# arduino.net
KiCad netlist of a schematic drawn in EAGLE
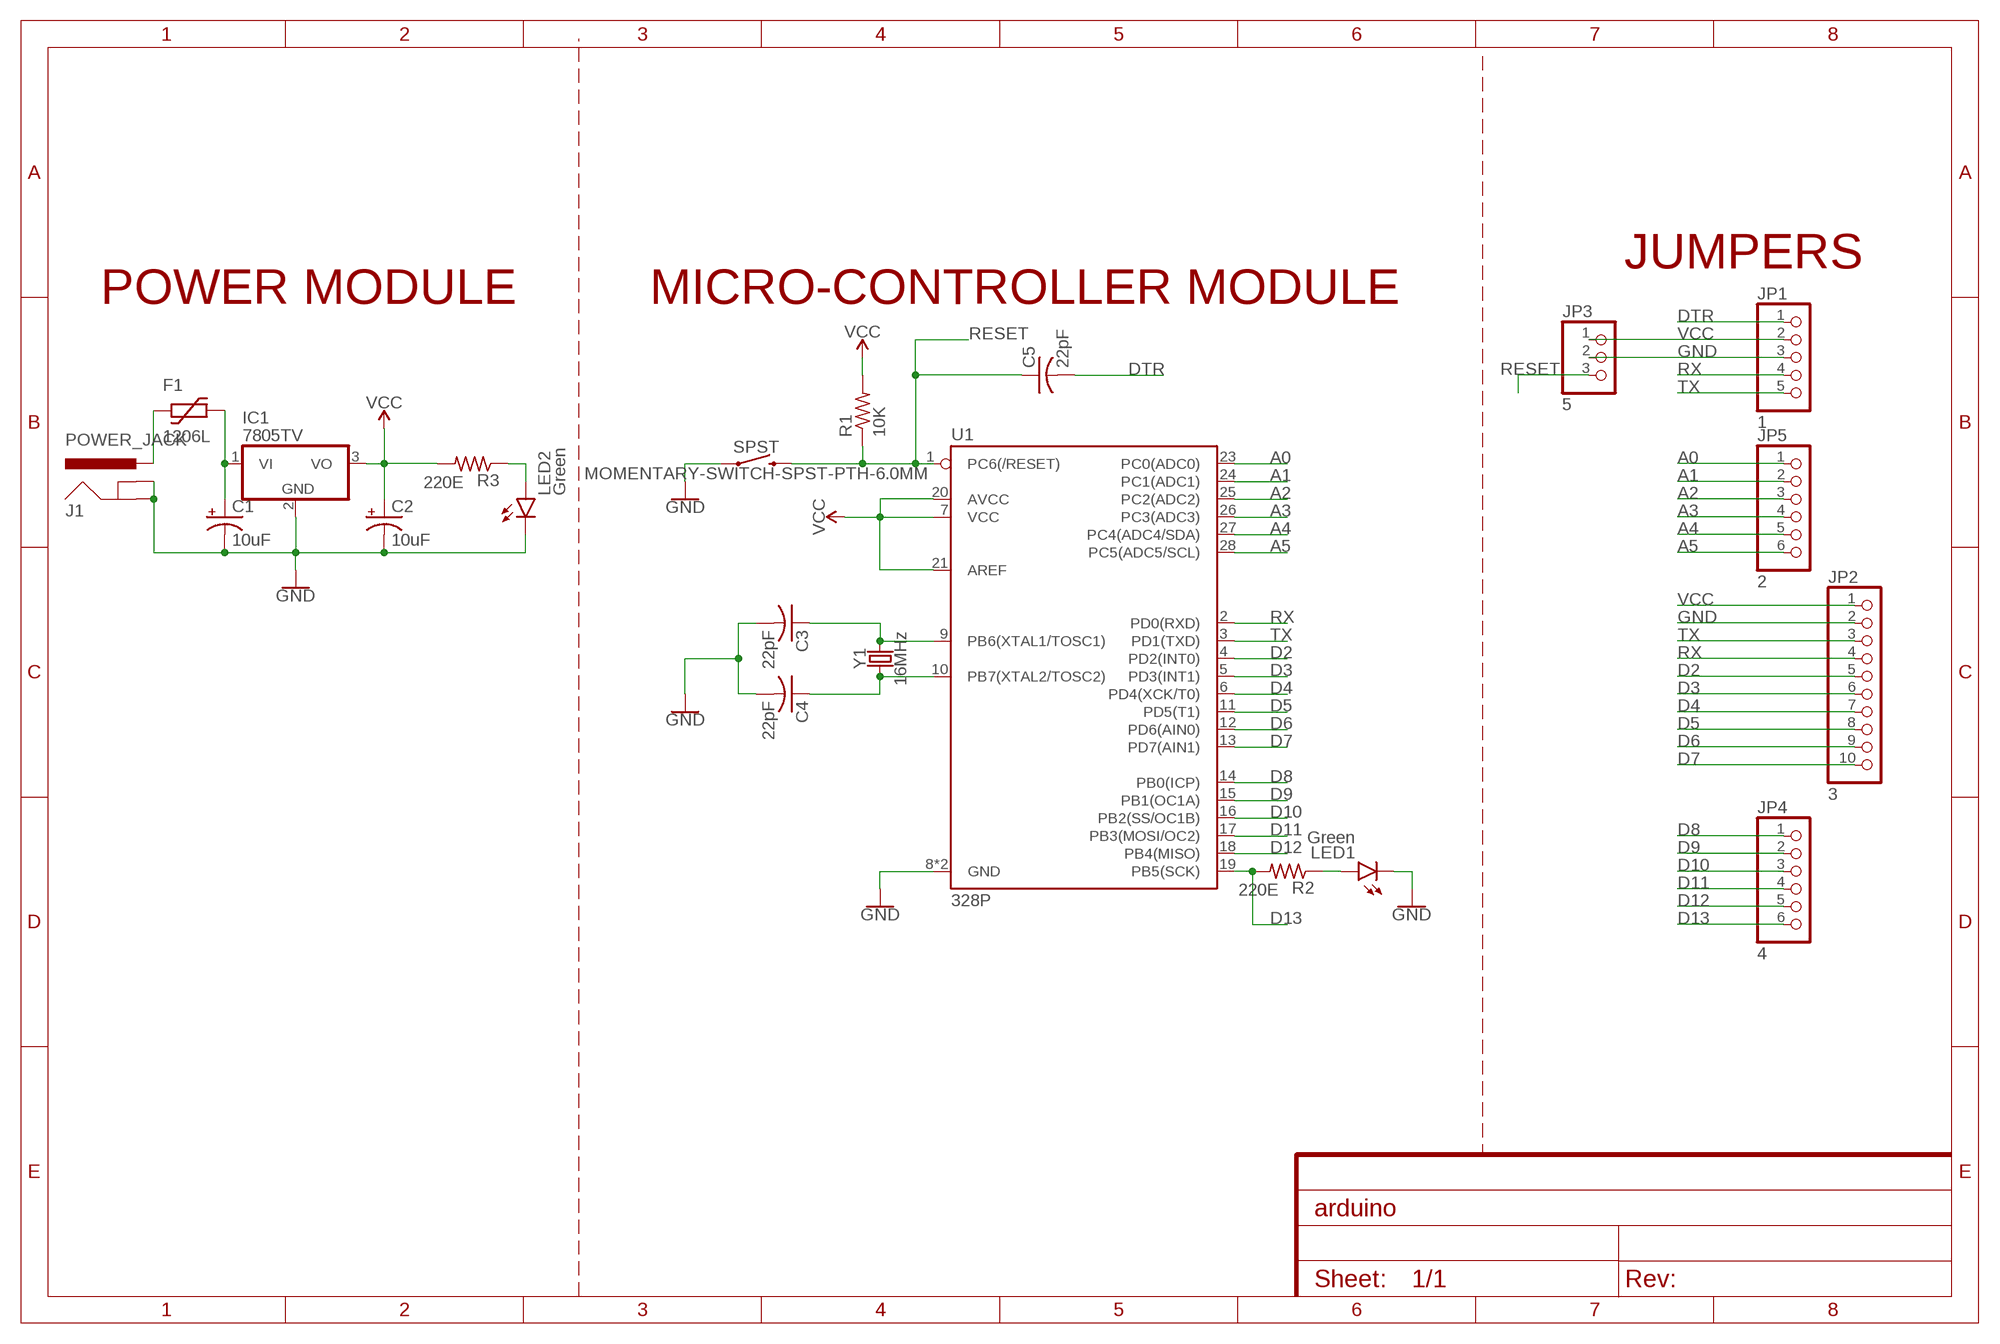
[diagram p0: schematic, sheet 1]

(export (version "E")
  (design (tool "Eeschema 10.0.6"))
  (components
    (comp (ref "C1")
      (value "10uF")
      (footprint "eagle-import:E2,5-6E")
      (libsource (lib "eagle-import") (part "CPOL-USE2,5-6E"))
    )
    (comp (ref "C2")
      (value "10uF")
      (footprint "eagle-import:E2,5-6E")
      (libsource (lib "eagle-import") (part "CPOL-USE2,5-6E"))
    )
    (comp (ref "C3")
      (value "22pF")
      (footprint "eagle-import:C025-024X044")
      (libsource (lib "eagle-import") (part "C-US025-024X044"))
    )
    (comp (ref "C4")
      (value "22pF")
      (footprint "eagle-import:C025-024X044")
      (libsource (lib "eagle-import") (part "C-US025-024X044"))
    )
    (comp (ref "C5")
      (value "22pF")
      (footprint "eagle-import:C025-024X044")
      (libsource (lib "eagle-import") (part "C-US025-024X044"))
    )
    (comp (ref "F1")
      (value "1206L")
      (footprint "eagle-import:1206L")
      (libsource (lib "eagle-import") (part "1206L"))
    )
    (comp (ref "IC1")
      (value "7805TV")
      (footprint "eagle-import:TO220V")
      (libsource (lib "eagle-import") (part "78TV05"))
    )
    (comp (ref "J1")
      (value "POWER_JACK")
      (footprint "eagle-import:POWER_JACK_PTH")
      (libsource (lib "eagle-import") (part "POWER_JACK"))
    )
    (comp (ref "JP1")
      (value "1")
      (footprint "eagle-import:1X05")
      (libsource (lib "eagle-import") (part "PINHD-1X5"))
    )
    (comp (ref "JP2")
      (value "3")
      (footprint "eagle-import:1X10")
      (libsource (lib "eagle-import") (part "PINHD-1X10"))
    )
    (comp (ref "JP3")
      (value "5")
      (footprint "eagle-import:1X03")
      (libsource (lib "eagle-import") (part "PINHD-1X3"))
    )
    (comp (ref "JP4")
      (value "4")
      (footprint "eagle-import:1X06")
      (libsource (lib "eagle-import") (part "PINHD-1X6"))
    )
    (comp (ref "JP5")
      (value "2")
      (footprint "eagle-import:1X06")
      (libsource (lib "eagle-import") (part "PINHD-1X6"))
    )
    (comp (ref "LED1")
      (value "Green")
      (footprint "eagle-import:LED3MM")
      (libsource (lib "eagle-import") (part "LED3MM"))
    )
    (comp (ref "LED2")
      (value "Green")
      (footprint "eagle-import:LED3MM")
      (libsource (lib "eagle-import") (part "LED3MM"))
    )
    (comp (ref "R1")
      (value "10K")
      (footprint "eagle-import:0204_7")
      (libsource (lib "eagle-import") (part "R-US_0204/7"))
    )
    (comp (ref "R2")
      (value "220E")
      (footprint "eagle-import:0204_7")
      (libsource (lib "eagle-import") (part "R-US_0204/7"))
    )
    (comp (ref "R3")
      (value "220E")
      (footprint "eagle-import:0204_7")
      (libsource (lib "eagle-import") (part "R-US_0204/7"))
    )
    (comp (ref "SPST")
      (value "MOMENTARY-SWITCH-SPST-PTH-6.0MM")
      (footprint "eagle-import:TACTILE_SWITCH_PTH_6.0MM")
      (libsource (lib "eagle-import") (part "MOMENTARY-SWITCH-SPST-PTH-6.0MM"))
    )
    (comp (ref "U1")
      (value "328P")
      (footprint "eagle-import:DIP28")
      (libsource (lib "eagle-import") (part "ATMEGA328P_PDIP"))
    )
    (comp (ref "Y1")
      (value "16MHz")
      (footprint "eagle-import:HC49US")
      (libsource (lib "eagle-import") (part "CRYSTAL-16MHZPTH-HC49US"))
    )
  )
  (nets
    (net (code "1") (name "/A0") (class "Default")
      (node (ref "JP5") (pin "1") (pinfunction "1_1") (pintype "passive"))
      (node (ref "U1") (pin "23") (pinfunction "PC0(ADC0)_23") (pintype "bidirectional"))
    )
    (net (code "2") (name "/A1") (class "Default")
      (node (ref "JP5") (pin "2") (pinfunction "2_2") (pintype "passive"))
      (node (ref "U1") (pin "24") (pinfunction "PC1(ADC1)_24") (pintype "bidirectional"))
    )
    (net (code "3") (name "/A2") (class "Default")
      (node (ref "JP5") (pin "3") (pinfunction "3_3") (pintype "passive"))
      (node (ref "U1") (pin "25") (pinfunction "PC2(ADC2)_25") (pintype "bidirectional"))
    )
    (net (code "4") (name "/A3") (class "Default")
      (node (ref "JP5") (pin "4") (pinfunction "4_4") (pintype "passive"))
      (node (ref "U1") (pin "26") (pinfunction "PC3(ADC3)_26") (pintype "bidirectional"))
    )
    (net (code "5") (name "/A4") (class "Default")
      (node (ref "JP5") (pin "5") (pinfunction "5_5") (pintype "passive"))
      (node (ref "U1") (pin "27") (pinfunction "PC4(ADC4/SDA)_27") (pintype "bidirectional"))
    )
    (net (code "6") (name "/A5") (class "Default")
      (node (ref "JP5") (pin "6") (pinfunction "6_6") (pintype "passive"))
      (node (ref "U1") (pin "28") (pinfunction "PC5(ADC5/SCL)_28") (pintype "bidirectional"))
    )
    (net (code "7") (name "/D2") (class "Default")
      (node (ref "JP2") (pin "5") (pinfunction "5_5") (pintype "passive"))
      (node (ref "U1") (pin "4") (pinfunction "PD2(INT0)_4") (pintype "bidirectional"))
    )
    (net (code "8") (name "/D3") (class "Default")
      (node (ref "JP2") (pin "6") (pinfunction "6_6") (pintype "passive"))
      (node (ref "U1") (pin "5") (pinfunction "PD3(INT1)_5") (pintype "bidirectional"))
    )
    (net (code "9") (name "/D4") (class "Default")
      (node (ref "JP2") (pin "7") (pinfunction "7_7") (pintype "passive"))
      (node (ref "U1") (pin "6") (pinfunction "PD4(XCK/T0)_6") (pintype "bidirectional"))
    )
    (net (code "10") (name "/D5") (class "Default")
      (node (ref "JP2") (pin "8") (pinfunction "8_8") (pintype "passive"))
      (node (ref "U1") (pin "11") (pinfunction "PD5(T1)_11") (pintype "bidirectional"))
    )
    (net (code "11") (name "/D6") (class "Default")
      (node (ref "JP2") (pin "9") (pinfunction "9_9") (pintype "passive"))
      (node (ref "U1") (pin "12") (pinfunction "PD6(AIN0)_12") (pintype "bidirectional"))
    )
    (net (code "12") (name "/D7") (class "Default")
      (node (ref "JP2") (pin "10") (pinfunction "10_10") (pintype "passive"))
      (node (ref "U1") (pin "13") (pinfunction "PD7(AIN1)_13") (pintype "bidirectional"))
    )
    (net (code "13") (name "/D8") (class "Default")
      (node (ref "JP4") (pin "1") (pinfunction "1_1") (pintype "passive"))
      (node (ref "U1") (pin "14") (pinfunction "PB0(ICP)_14") (pintype "bidirectional"))
    )
    (net (code "14") (name "/D9") (class "Default")
      (node (ref "JP4") (pin "2") (pinfunction "2_2") (pintype "passive"))
      (node (ref "U1") (pin "15") (pinfunction "PB1(OC1A)_15") (pintype "bidirectional"))
    )
    (net (code "15") (name "/D10") (class "Default")
      (node (ref "JP4") (pin "3") (pinfunction "3_3") (pintype "passive"))
      (node (ref "U1") (pin "16") (pinfunction "PB2(SS/OC1B)_16") (pintype "bidirectional"))
    )
    (net (code "16") (name "/D11") (class "Default")
      (node (ref "JP4") (pin "4") (pinfunction "4_4") (pintype "passive"))
      (node (ref "U1") (pin "17") (pinfunction "PB3(MOSI/OC2)_17") (pintype "bidirectional"))
    )
    (net (code "17") (name "/D12") (class "Default")
      (node (ref "JP4") (pin "5") (pinfunction "5_5") (pintype "passive"))
      (node (ref "U1") (pin "18") (pinfunction "PB4(MISO)_18") (pintype "bidirectional"))
    )
    (net (code "18") (name "/D13") (class "Default")
      (node (ref "JP4") (pin "6") (pinfunction "6_6") (pintype "passive"))
      (node (ref "R2") (pin "2") (pinfunction "2_2") (pintype "passive"))
      (node (ref "U1") (pin "19") (pinfunction "PB5(SCK)_19") (pintype "bidirectional"))
    )
    (net (code "19") (name "/DTR") (class "Default")
      (node (ref "C5") (pin "2") (pinfunction "2_2") (pintype "passive"))
      (node (ref "JP1") (pin "1") (pinfunction "1_1") (pintype "passive"))
    )
    (net (code "20") (name "/RESET") (class "Default")
      (node (ref "C5") (pin "1") (pinfunction "1_1") (pintype "passive"))
      (node (ref "JP3") (pin "3") (pinfunction "3_3") (pintype "passive"))
      (node (ref "R1") (pin "1") (pinfunction "1_1") (pintype "passive"))
      (node (ref "SPST") (pin "3") (pinfunction "2_3") (pintype "passive"))
      (node (ref "U1") (pin "1") (pinfunction "PC6(/RESET)_1") (pintype "bidirectional"))
    )
    (net (code "21") (name "/RX") (class "Default")
      (node (ref "JP1") (pin "4") (pinfunction "4_4") (pintype "passive"))
      (node (ref "JP2") (pin "4") (pinfunction "4_4") (pintype "passive"))
      (node (ref "U1") (pin "2") (pinfunction "PD0(RXD)_2") (pintype "bidirectional"))
    )
    (net (code "22") (name "/TX") (class "Default")
      (node (ref "JP1") (pin "5") (pinfunction "5_5") (pintype "passive"))
      (node (ref "JP2") (pin "3") (pinfunction "3_3") (pintype "passive"))
      (node (ref "U1") (pin "3") (pinfunction "PD1(TXD)_3") (pintype "bidirectional"))
    )
    (net (code "23") (name "GND") (class "Default")
      (node (ref "C1") (pin "-") (pinfunction "-_-") (pintype "passive"))
      (node (ref "C2") (pin "-") (pinfunction "-_-") (pintype "passive"))
      (node (ref "C3") (pin "2") (pinfunction "2_2") (pintype "passive"))
      (node (ref "C4") (pin "2") (pinfunction "2_2") (pintype "passive"))
      (node (ref "IC1") (pin "2") (pinfunction "GND_2") (pintype "passive"))
      (node (ref "J1") (pin "GND") (pinfunction "GND_GND") (pintype "bidirectional"))
      (node (ref "J1") (pin "GNDBREAK") (pinfunction "GNDBREAK_GNDBREAK") (pintype "bidirectional"))
      (node (ref "JP1") (pin "3") (pinfunction "3_3") (pintype "passive"))
      (node (ref "JP2") (pin "2") (pinfunction "2_2") (pintype "passive"))
      (node (ref "JP3") (pin "2") (pinfunction "2_2") (pintype "passive"))
      (node (ref "LED1") (pin "K") (pinfunction "C_K") (pintype "passive"))
      (node (ref "LED2") (pin "K") (pinfunction "C_K") (pintype "passive"))
      (node (ref "SPST") (pin "1") (pinfunction "1_1") (pintype "passive"))
      (node (ref "U1") (pin "22") (pinfunction "GND_22") (pintype "bidirectional"))
      (node (ref "U1") (pin "8") (pinfunction "GND_8") (pintype "bidirectional"))
    )
    (net (code "24") (name "Net-(F1-1)") (class "Default")
      (node (ref "F1") (pin "P$1") (pinfunction "1_P$1") (pintype "passive"))
      (node (ref "J1") (pin "PWR") (pinfunction "PWR_PWR") (pintype "bidirectional"))
    )
    (net (code "25") (name "Net-(F1-2)") (class "Default")
      (node (ref "C1") (pin "+") (pinfunction "+_+") (pintype "passive"))
      (node (ref "F1") (pin "P$2") (pinfunction "2_P$2") (pintype "passive"))
      (node (ref "IC1") (pin "1") (pinfunction "VI_1") (pintype "input"))
    )
    (net (code "26") (name "Net-(LED1-PadA)") (class "Default")
      (node (ref "LED1") (pin "A") (pinfunction "A_A") (pintype "passive"))
      (node (ref "R2") (pin "1") (pinfunction "1_1") (pintype "passive"))
    )
    (net (code "27") (name "Net-(LED2-PadA)") (class "Default")
      (node (ref "LED2") (pin "A") (pinfunction "A_A") (pintype "passive"))
      (node (ref "R3") (pin "1") (pinfunction "1_1") (pintype "passive"))
    )
    (net (code "28") (name "Net-(U1-PB6(XTAL1{slash}TOSC1))") (class "Default")
      (node (ref "C3") (pin "1") (pinfunction "1_1") (pintype "passive"))
      (node (ref "U1") (pin "9") (pinfunction "PB6(XTAL1/TOSC1)_9") (pintype "bidirectional"))
      (node (ref "Y1") (pin "2") (pinfunction "2_2") (pintype "passive"))
    )
    (net (code "29") (name "Net-(U1-PB7(XTAL2{slash}TOSC2))") (class "Default")
      (node (ref "C4") (pin "1") (pinfunction "1_1") (pintype "passive"))
      (node (ref "U1") (pin "10") (pinfunction "PB7(XTAL2/TOSC2)_10") (pintype "bidirectional"))
      (node (ref "Y1") (pin "1") (pinfunction "1_1") (pintype "passive"))
    )
    (net (code "30") (name "VCC") (class "Default")
      (node (ref "C2") (pin "+") (pinfunction "+_+") (pintype "passive"))
      (node (ref "IC1") (pin "3") (pinfunction "VO_3") (pintype "passive"))
      (node (ref "JP1") (pin "2") (pinfunction "2_2") (pintype "passive"))
      (node (ref "JP2") (pin "1") (pinfunction "1_1") (pintype "passive"))
      (node (ref "JP3") (pin "1") (pinfunction "1_1") (pintype "passive"))
      (node (ref "R1") (pin "2") (pinfunction "2_2") (pintype "passive"))
      (node (ref "R3") (pin "2") (pinfunction "2_2") (pintype "passive"))
      (node (ref "U1") (pin "20") (pinfunction "AVCC_20") (pintype "bidirectional"))
      (node (ref "U1") (pin "21") (pinfunction "AREF_21") (pintype "bidirectional"))
      (node (ref "U1") (pin "7") (pinfunction "VCC_7") (pintype "bidirectional"))
    )
  )
)
